# SCH_Personal-Card.net
KiCad netlist of a schematic drawn in EasyEDA
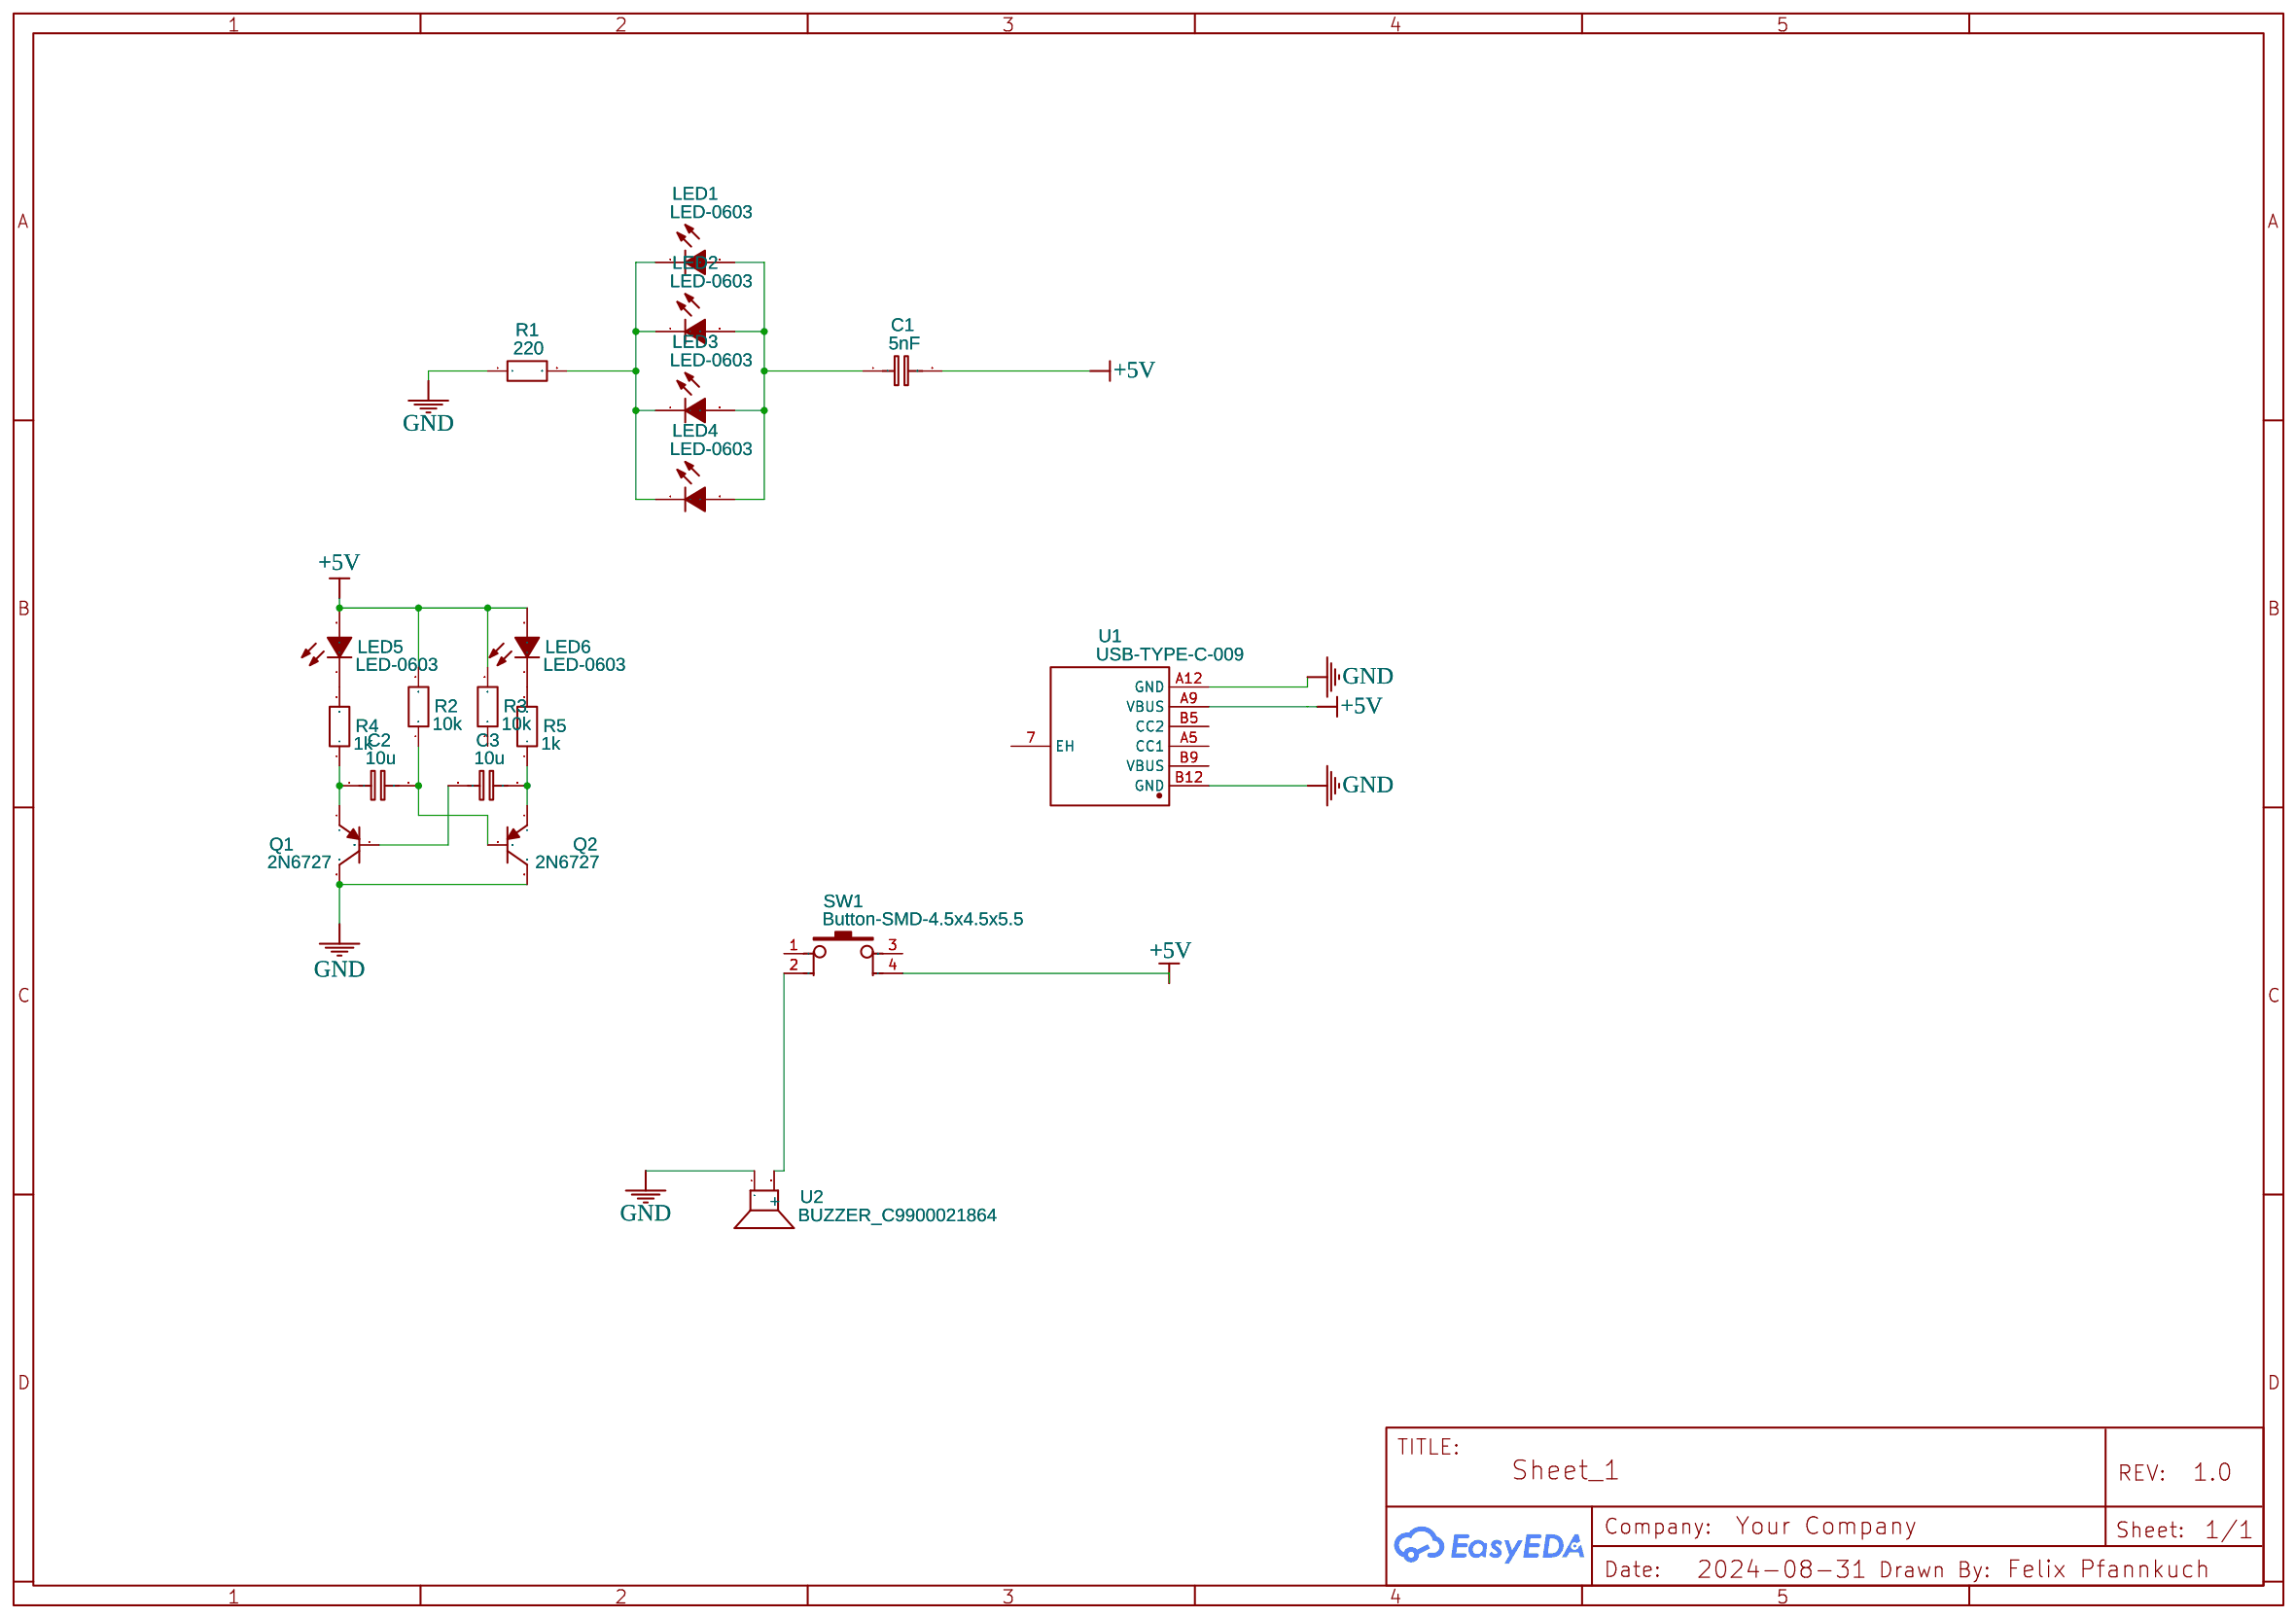
[diagram p0: schematic sheet]

(export (version "E")
  (design (tool "Eeschema 10.0.6"))
  (components
    (comp (ref "C1") (value "5nF") (libsource (lib "") (part "C_0603_EU_1")))
    (comp (ref "C2") (value "10u") (libsource (lib "") (part "C_0603_EU")))
    (comp (ref "C3") (value "10u") (libsource (lib "") (part "C_0603_EU")))
    (comp (ref "LED1") (value "LED-0603") (libsource (lib "") (part "LED-0603")))
    (comp (ref "LED2") (value "LED-0603") (libsource (lib "") (part "LED-0603")))
    (comp (ref "LED3") (value "LED-0603") (libsource (lib "") (part "LED-0603")))
    (comp (ref "LED4") (value "LED-0603") (libsource (lib "") (part "LED-0603")))
    (comp (ref "LED5") (value "LED-0603") (libsource (lib "") (part "LED-0603_1")))
    (comp (ref "LED6") (value "LED-0603") (libsource (lib "") (part "LED-0603_1")))
    (comp (ref "Q1")
      (value "2N6727")
      (fields (field (name "Manufacturer") "CJ"))
      (libsource (lib "") (part "2N6727_1"))
    )
    (comp (ref "Q2")
      (value "2N6727")
      (fields (field (name "Manufacturer") "CJ"))
      (libsource (lib "") (part "2N6727"))
    )
    (comp (ref "R1") (value "220") (libsource (lib "") (part "R_0603_EU")))
    (comp (ref "R2") (value "10k") (libsource (lib "") (part "R_0603_EU_1")))
    (comp (ref "R3") (value "10k") (libsource (lib "") (part "R_0603_EU_1")))
    (comp (ref "R4") (value "1k") (libsource (lib "") (part "R_0603_EU_1")))
    (comp (ref "R5") (value "1k") (libsource (lib "") (part "R_0603_EU_1")))
    (comp (ref "SW1")
      (value "Button-SMD-4.5x4.5x5.5")
      (fields
        (field (name "Manufacturer Part") "4.5*4.5*5.5 Plastic head,260G, 0.25mm,SMD")
        (field (name "Manufacturer") "BBJ")
      )
      (libsource (lib "") (part "Button-SMD-4.5x4.5x5.5"))
    )
    (comp (ref "U1")
      (value "USB-TYPE-C-009")
      (fields (field (name "Manufacturer") "DEALON(德艺隆)"))
      (libsource (lib "") (part "USB-TYPE-C-009"))
    )
    (comp (ref "U2")
      (value "BUZZER_C9900021864")
      (fields (field (name "Manufacturer Part") "BUZZER"))
      (libsource (lib "") (part "BUZZER_C9900021864"))
    )
  )
  (nets
    (net (code "1") (name "+5V") (class "Default")
      (node (ref "C1") (pin "2") (pinfunction "2_2") (pintype "unspecified"))
      (node (ref "LED5") (pin "2") (pinfunction "+_2") (pintype "input"))
      (node (ref "LED6") (pin "2") (pinfunction "+_2") (pintype "input"))
      (node (ref "R2") (pin "2") (pinfunction "2_2") (pintype "unspecified"))
      (node (ref "R3") (pin "2") (pinfunction "2_2") (pintype "unspecified"))
      (node (ref "SW1") (pin "4") (pinfunction "4_4") (pintype "input"))
      (node (ref "U1") (pin "A9") (pinfunction "VBUS_A9") (pintype "unspecified"))
    )
    (net (code "2") (name "GND") (class "Default")
      (node (ref "Q1") (pin "3") (pinfunction "C_3") (pintype "unspecified"))
      (node (ref "Q2") (pin "3") (pinfunction "C_3") (pintype "unspecified"))
      (node (ref "R1") (pin "1") (pinfunction "1_1") (pintype "unspecified"))
      (node (ref "U1") (pin "A12") (pinfunction "GND_A12") (pintype "unspecified"))
      (node (ref "U1") (pin "B12") (pinfunction "GND_B12") (pintype "unspecified"))
      (node (ref "U2") (pin "1") (pinfunction "1_1") (pintype "unspecified"))
    )
    (net (code "3") (name "Net-(LED1-+)") (class "Default")
      (node (ref "C1") (pin "1") (pinfunction "1_1") (pintype "unspecified"))
      (node (ref "LED1") (pin "2") (pinfunction "+_2") (pintype "input"))
      (node (ref "LED2") (pin "2") (pinfunction "+_2") (pintype "input"))
      (node (ref "LED3") (pin "2") (pinfunction "+_2") (pintype "input"))
      (node (ref "LED4") (pin "2") (pinfunction "+_2") (pintype "input"))
    )
    (net (code "4") (name "Net-(LED1--)") (class "Default")
      (node (ref "LED1") (pin "1") (pinfunction "-_1") (pintype "input"))
      (node (ref "LED2") (pin "1") (pinfunction "-_1") (pintype "input"))
      (node (ref "LED3") (pin "1") (pinfunction "-_1") (pintype "input"))
      (node (ref "LED4") (pin "1") (pinfunction "-_1") (pintype "input"))
      (node (ref "R1") (pin "2") (pinfunction "2_2") (pintype "unspecified"))
    )
    (net (code "5") (name "Net-(LED5--)") (class "Default")
      (node (ref "LED5") (pin "1") (pinfunction "-_1") (pintype "input"))
      (node (ref "R4") (pin "2") (pinfunction "2_2") (pintype "unspecified"))
    )
    (net (code "6") (name "Net-(LED6--)") (class "Default")
      (node (ref "LED6") (pin "1") (pinfunction "-_1") (pintype "input"))
      (node (ref "R5") (pin "2") (pinfunction "2_2") (pintype "unspecified"))
    )
    (net (code "7") (name "Net-(Q1-B)") (class "Default")
      (node (ref "C3") (pin "1") (pinfunction "1_1") (pintype "unspecified"))
      (node (ref "Q1") (pin "2") (pinfunction "B_2") (pintype "unspecified"))
    )
    (net (code "8") (name "Net-(Q1-E)") (class "Default")
      (node (ref "C2") (pin "1") (pinfunction "1_1") (pintype "unspecified"))
      (node (ref "Q1") (pin "1") (pinfunction "E_1") (pintype "unspecified"))
      (node (ref "R4") (pin "1") (pinfunction "1_1") (pintype "unspecified"))
    )
    (net (code "9") (name "Net-(Q2-B)") (class "Default")
      (node (ref "C2") (pin "2") (pinfunction "2_2") (pintype "unspecified"))
      (node (ref "Q2") (pin "2") (pinfunction "B_2") (pintype "unspecified"))
      (node (ref "R2") (pin "1") (pinfunction "1_1") (pintype "unspecified"))
    )
    (net (code "10") (name "Net-(Q2-E)") (class "Default")
      (node (ref "C3") (pin "2") (pinfunction "2_2") (pintype "unspecified"))
      (node (ref "Q2") (pin "1") (pinfunction "E_1") (pintype "unspecified"))
      (node (ref "R5") (pin "1") (pinfunction "1_1") (pintype "unspecified"))
    )
    (net (code "11") (name "Net-(U2-+)") (class "Default")
      (node (ref "SW1") (pin "2") (pinfunction "2_2") (pintype "input"))
      (node (ref "U2") (pin "2") (pinfunction "+_2") (pintype "unspecified"))
    )
    (net (code "12") (name "unconnected-(R3-Pad1)") (class "Default")
      (node (ref "R3") (pin "1") (pinfunction "1_1") (pintype "unspecified"))
    )
    (net (code "13") (name "unconnected-(SW1-Pad1)") (class "Default")
      (node (ref "SW1") (pin "1") (pinfunction "1_1") (pintype "input"))
    )
    (net (code "14") (name "unconnected-(SW1-Pad3)") (class "Default")
      (node (ref "SW1") (pin "3") (pinfunction "3_3") (pintype "input"))
    )
    (net (code "15") (name "unconnected-(U1-CC1-PadA5)") (class "Default")
      (node (ref "U1") (pin "A5") (pinfunction "CC1_A5") (pintype "unspecified"))
    )
    (net (code "16") (name "unconnected-(U1-CC2-PadB5)") (class "Default")
      (node (ref "U1") (pin "B5") (pinfunction "CC2_B5") (pintype "unspecified"))
    )
    (net (code "17") (name "unconnected-(U1-EH-Pad7)") (class "Default")
      (node (ref "U1") (pin "7") (pinfunction "EH_7") (pintype "unspecified"))
    )
    (net (code "18") (name "unconnected-(U1-VBUS-PadB9)") (class "Default")
      (node (ref "U1") (pin "B9") (pinfunction "VBUS_B9") (pintype "unspecified"))
    )
  )
)
